# FTDI_prog.net
KiCad netlist of a schematic drawn in EAGLE
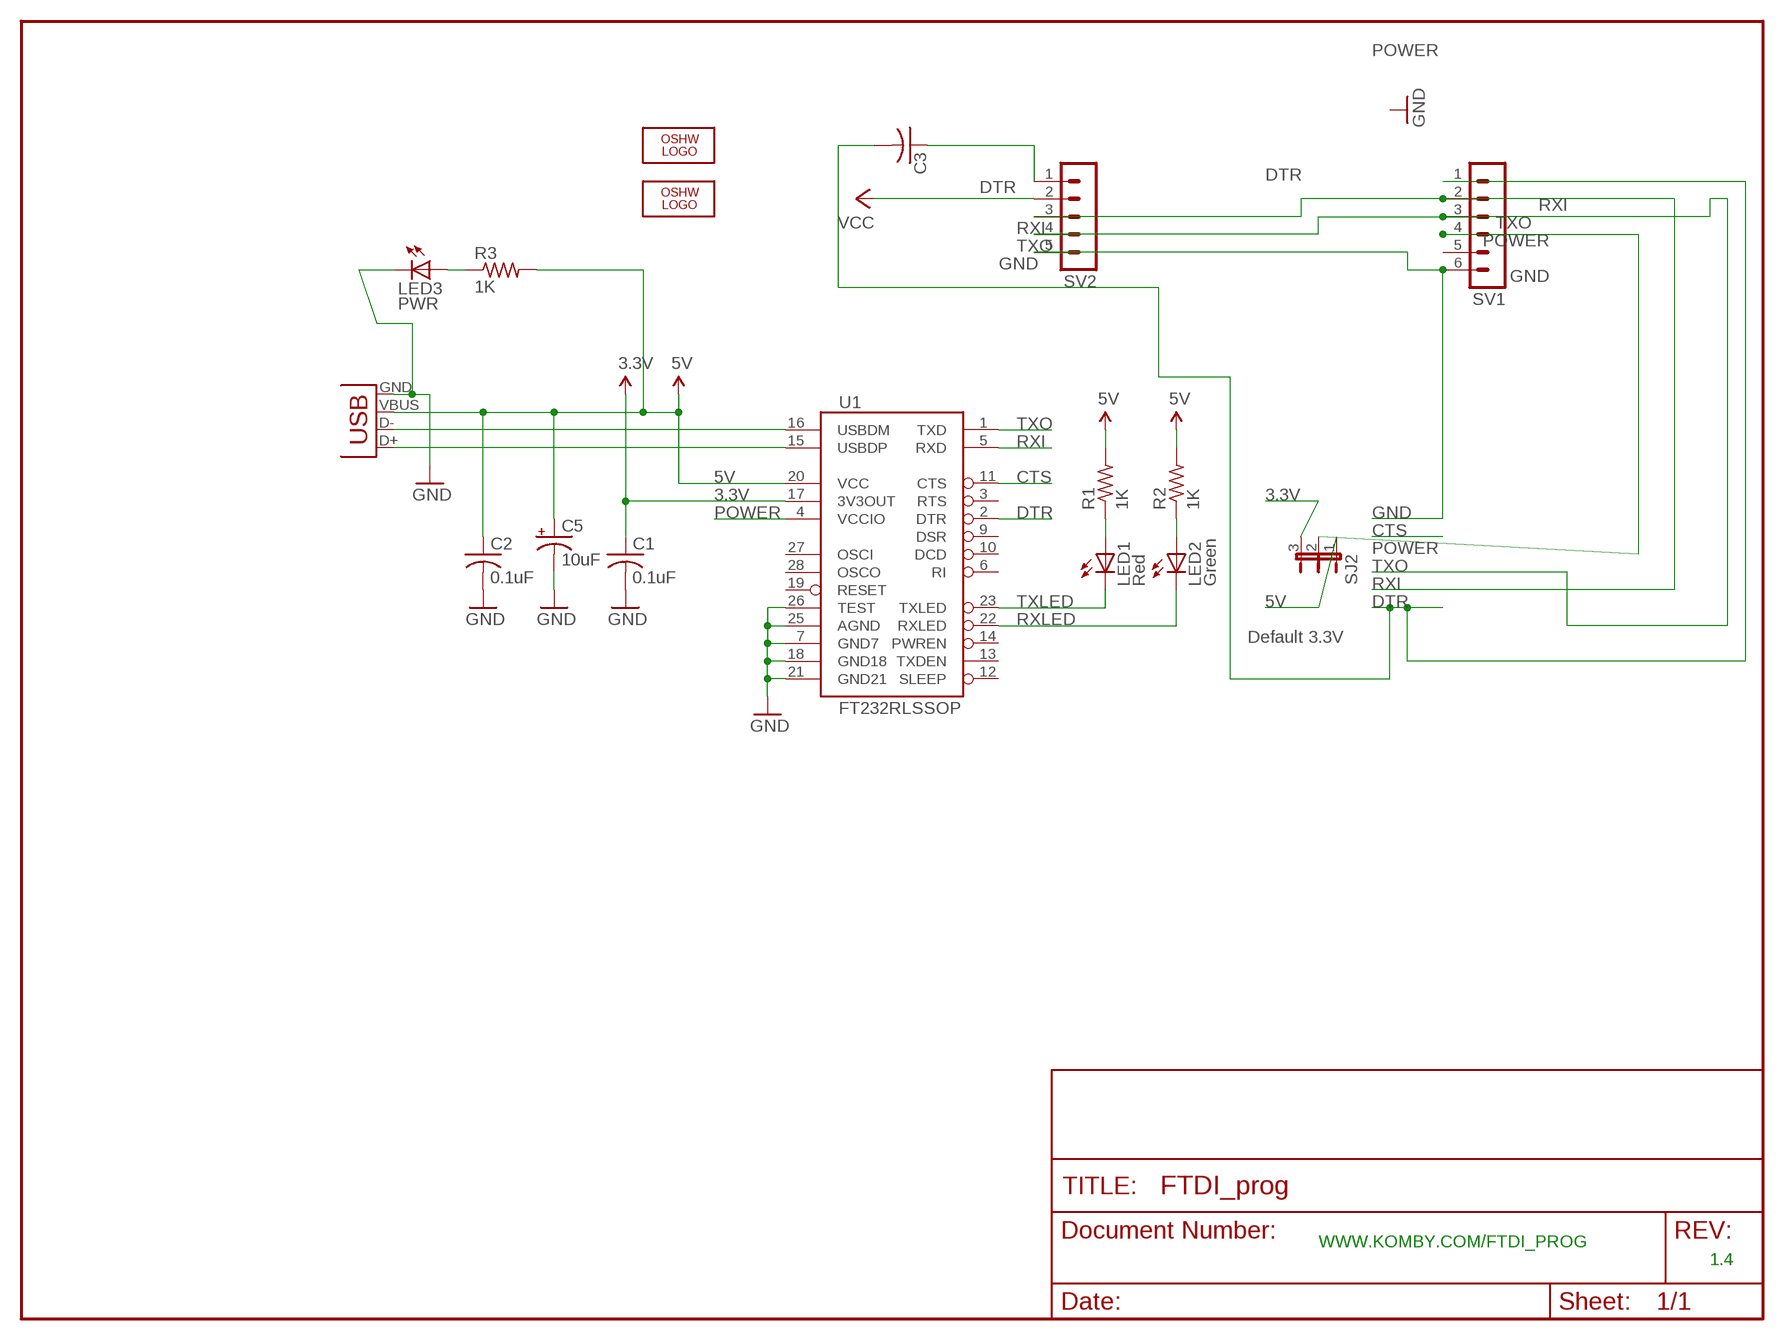
[diagram p0: schematic, sheet 1]

(export (version "E")
  (design (tool "Eeschema 10.0.6"))
  (components
    (comp (ref "C1")
      (value "0.1uF")
      (footprint "eagle-import:C025-024X044")
      (libsource (lib "eagle-import") (part "C-US025-024X044"))
    )
    (comp (ref "C2")
      (value "0.1uF")
      (footprint "eagle-import:C025-024X044")
      (libsource (lib "eagle-import") (part "C-US025-024X044"))
    )
    (comp (ref "C3")
      (value "C-US025-024X044")
      (footprint "eagle-import:C025-024X044")
      (libsource (lib "eagle-import") (part "C-US025-024X044"))
    )
    (comp (ref "C5")
      (value "10uF")
      (footprint "eagle-import:E1,8-4")
      (libsource (lib "eagle-import") (part "CPOL-USE1.8-4"))
    )
    (comp (ref "LED1")
      (value "Red")
      (footprint "eagle-import:LED3MM")
      (libsource (lib "eagle-import") (part "LED3MM"))
    )
    (comp (ref "LED2")
      (value "Green")
      (footprint "eagle-import:LED3MM")
      (libsource (lib "eagle-import") (part "LED3MM"))
    )
    (comp (ref "LED3")
      (value "PWR")
      (footprint "eagle-import:LED3MM")
      (libsource (lib "eagle-import") (part "LED3MM"))
    )
    (comp (ref "LOGO1")
      (value "OSHW_LOGO_6MILX0070-NT")
      (footprint "eagle-import:OSHW_6X70_NOTEXT")
      (libsource (lib "eagle-import") (part "OSHW_LOGO_6MILX0070-NT"))
    )
    (comp (ref "LOGO2")
      (value "OSHW_LOGO_6MILX0070-NT")
      (footprint "eagle-import:OSHW_6X70_NOTEXT")
      (libsource (lib "eagle-import") (part "OSHW_LOGO_6MILX0070-NT"))
    )
    (comp (ref "R1")
      (value "1K")
      (footprint "eagle-import:0207_7")
      (libsource (lib "eagle-import") (part "R-US_0207/7"))
    )
    (comp (ref "R2")
      (value "1K")
      (footprint "eagle-import:0207_7")
      (libsource (lib "eagle-import") (part "R-US_0207/7"))
    )
    (comp (ref "R3")
      (value "1K")
      (footprint "eagle-import:0207_7")
      (libsource (lib "eagle-import") (part "R-US_0207/7"))
    )
    (comp (ref "SJ2")
      (value "JP2E")
      (footprint "eagle-import:JP2")
      (libsource (lib "eagle-import") (part "JP2E"))
    )
    (comp (ref "SV1")
      (value "MA06-1")
      (footprint "eagle-import:MA06-1")
      (libsource (lib "eagle-import") (part "MA06-1"))
    )
    (comp (ref "SV2")
      (value "MA05-1")
      (footprint "eagle-import:MA05-1")
      (libsource (lib "eagle-import") (part "MA05-1"))
    )
    (comp (ref "U1")
      (value "FT232RLSSOP")
      (footprint "eagle-import:SSOP28DB")
      (libsource (lib "eagle-import") (part "FT232RLSSOP"))
    )
    (comp (ref "X2")
      (value "USB-SMD-NS")
      (footprint "eagle-import:USB-MINIB-NOSTOP")
      (libsource (lib "eagle-import") (part "USB-SMD-NS"))
    )
  )
  (nets
    (net (code "1") (name "/CTS") (class "Default")
      (node (ref "U1") (pin "11") (pinfunction "CTS_11") (pintype "input"))
    )
    (net (code "2") (name "/DTR") (class "Default")
      (node (ref "C3") (pin "2") (pinfunction "2_2") (pintype "passive"))
      (node (ref "SV1") (pin "1") (pinfunction "1_1") (pintype "passive"))
      (node (ref "U1") (pin "2") (pinfunction "DTR_2") (pintype "output"))
    )
    (net (code "3") (name "/RXI") (class "Default")
      (node (ref "SV1") (pin "2") (pinfunction "2_2") (pintype "passive"))
      (node (ref "SV2") (pin "3") (pinfunction "3_3") (pintype "passive"))
      (node (ref "U1") (pin "5") (pinfunction "RXD_5") (pintype "input"))
    )
    (net (code "4") (name "/RXLED") (class "Default")
      (node (ref "LED2") (pin "K") (pinfunction "C_K") (pintype "passive"))
      (node (ref "U1") (pin "22") (pinfunction "RXLED_22") (pintype "input"))
    )
    (net (code "5") (name "/TXLED") (class "Default")
      (node (ref "LED1") (pin "K") (pinfunction "C_K") (pintype "passive"))
      (node (ref "U1") (pin "23") (pinfunction "TXLED_23") (pintype "input"))
    )
    (net (code "6") (name "/TXO") (class "Default")
      (node (ref "SV1") (pin "3") (pinfunction "3_3") (pintype "passive"))
      (node (ref "SV2") (pin "4") (pinfunction "4_4") (pintype "passive"))
      (node (ref "U1") (pin "1") (pinfunction "TXD_1") (pintype "output"))
    )
    (net (code "7") (name "3.3V") (class "Default")
      (node (ref "C1") (pin "1") (pinfunction "1_1") (pintype "passive"))
      (node (ref "SJ2") (pin "3") (pinfunction "3_3") (pintype "passive"))
      (node (ref "U1") (pin "17") (pinfunction "3V3OUT_17") (pintype "output"))
    )
    (net (code "8") (name "5V") (class "Default")
      (node (ref "C2") (pin "1") (pinfunction "1_1") (pintype "passive"))
      (node (ref "C5") (pin "+") (pinfunction "+_+") (pintype "passive"))
      (node (ref "R1") (pin "2") (pinfunction "2_2") (pintype "passive"))
      (node (ref "R2") (pin "2") (pinfunction "2_2") (pintype "passive"))
      (node (ref "R3") (pin "2") (pinfunction "2_2") (pintype "passive"))
      (node (ref "SJ2") (pin "1") (pinfunction "1_1") (pintype "passive"))
      (node (ref "U1") (pin "20") (pinfunction "VCC_20") (pintype "power_in"))
      (node (ref "X2") (pin "VBUS") (pinfunction "VBUS_VBUS") (pintype "bidirectional"))
    )
    (net (code "9") (name "GND") (class "Default")
      (node (ref "C1") (pin "2") (pinfunction "2_2") (pintype "passive"))
      (node (ref "C2") (pin "2") (pinfunction "2_2") (pintype "passive"))
      (node (ref "C5") (pin "-") (pinfunction "-_-") (pintype "passive"))
      (node (ref "LED3") (pin "K") (pinfunction "C_K") (pintype "passive"))
      (node (ref "SV1") (pin "6") (pinfunction "6_6") (pintype "passive"))
      (node (ref "SV2") (pin "5") (pinfunction "5_5") (pintype "passive"))
      (node (ref "U1") (pin "18") (pinfunction "GND18_18") (pintype "power_in"))
      (node (ref "U1") (pin "21") (pinfunction "GND21_21") (pintype "power_in"))
      (node (ref "U1") (pin "25") (pinfunction "AGND_25") (pintype "power_in"))
      (node (ref "U1") (pin "26") (pinfunction "TEST_26") (pintype "input"))
      (node (ref "U1") (pin "7") (pinfunction "GND7_7") (pintype "power_in"))
      (node (ref "X2") (pin "GND") (pinfunction "GND_GND") (pintype "bidirectional"))
    )
    (net (code "10") (name "Net-(C3-Pad1)") (class "Default")
      (node (ref "C3") (pin "1") (pinfunction "1_1") (pintype "passive"))
      (node (ref "SV2") (pin "1") (pinfunction "1_1") (pintype "passive"))
    )
    (net (code "11") (name "Net-(LED1-PadA)") (class "Default")
      (node (ref "LED1") (pin "A") (pinfunction "A_A") (pintype "passive"))
      (node (ref "R1") (pin "1") (pinfunction "1_1") (pintype "passive"))
    )
    (net (code "12") (name "Net-(LED2-PadA)") (class "Default")
      (node (ref "LED2") (pin "A") (pinfunction "A_A") (pintype "passive"))
      (node (ref "R2") (pin "1") (pinfunction "1_1") (pintype "passive"))
    )
    (net (code "13") (name "Net-(LED3-PadA)") (class "Default")
      (node (ref "LED3") (pin "A") (pinfunction "A_A") (pintype "passive"))
      (node (ref "R3") (pin "1") (pinfunction "1_1") (pintype "passive"))
    )
    (net (code "14") (name "Net-(U1-USBDM)") (class "Default")
      (node (ref "U1") (pin "16") (pinfunction "USBDM_16") (pintype "bidirectional"))
      (node (ref "X2") (pin "D-") (pinfunction "D-_D-") (pintype "bidirectional"))
    )
    (net (code "15") (name "Net-(U1-USBDP)") (class "Default")
      (node (ref "U1") (pin "15") (pinfunction "USBDP_15") (pintype "bidirectional"))
      (node (ref "X2") (pin "D+") (pinfunction "D+_D+") (pintype "bidirectional"))
    )
    (net (code "16") (name "VCC") (class "Default")
      (node (ref "SJ2") (pin "2") (pinfunction "2_2") (pintype "passive"))
      (node (ref "SV1") (pin "4") (pinfunction "4_4") (pintype "passive"))
      (node (ref "SV2") (pin "2") (pinfunction "2_2") (pintype "passive"))
      (node (ref "U1") (pin "4") (pinfunction "VCCIO_4") (pintype "power_in"))
    )
    (net (code "17") (name "unconnected-(SV1-Pad5)") (class "Default")
      (node (ref "SV1") (pin "5") (pinfunction "5_5") (pintype "passive"))
    )
    (net (code "18") (name "unconnected-(U1-DCD-Pad10)") (class "Default")
      (node (ref "U1") (pin "10") (pinfunction "DCD_10") (pintype "input"))
    )
    (net (code "19") (name "unconnected-(U1-DSR-Pad9)") (class "Default")
      (node (ref "U1") (pin "9") (pinfunction "DSR_9") (pintype "input"))
    )
    (net (code "20") (name "unconnected-(U1-OSCI-Pad27)") (class "Default")
      (node (ref "U1") (pin "27") (pinfunction "OSCI_27") (pintype "input"))
    )
    (net (code "21") (name "unconnected-(U1-OSCO-Pad28)") (class "Default")
      (node (ref "U1") (pin "28") (pinfunction "OSCO_28") (pintype "output"))
    )
    (net (code "22") (name "unconnected-(U1-PWREN-Pad14)") (class "Default")
      (node (ref "U1") (pin "14") (pinfunction "PWREN_14") (pintype "input"))
    )
    (net (code "23") (name "unconnected-(U1-RESET-Pad19)") (class "Default")
      (node (ref "U1") (pin "19") (pinfunction "RESET_19") (pintype "input"))
    )
    (net (code "24") (name "unconnected-(U1-RI-Pad6)") (class "Default")
      (node (ref "U1") (pin "6") (pinfunction "RI_6") (pintype "input"))
    )
    (net (code "25") (name "unconnected-(U1-RTS-Pad3)") (class "Default")
      (node (ref "U1") (pin "3") (pinfunction "RTS_3") (pintype "output"))
    )
    (net (code "26") (name "unconnected-(U1-SLEEP-Pad12)") (class "Default")
      (node (ref "U1") (pin "12") (pinfunction "SLEEP_12") (pintype "input"))
    )
    (net (code "27") (name "unconnected-(U1-TXDEN-Pad13)") (class "Default")
      (node (ref "U1") (pin "13") (pinfunction "TXDEN_13") (pintype "input"))
    )
  )
)
